# plugV6-Relay-NC_5x5cm_SMD0805-2.net
KiCad netlist of a schematic drawn in EAGLE
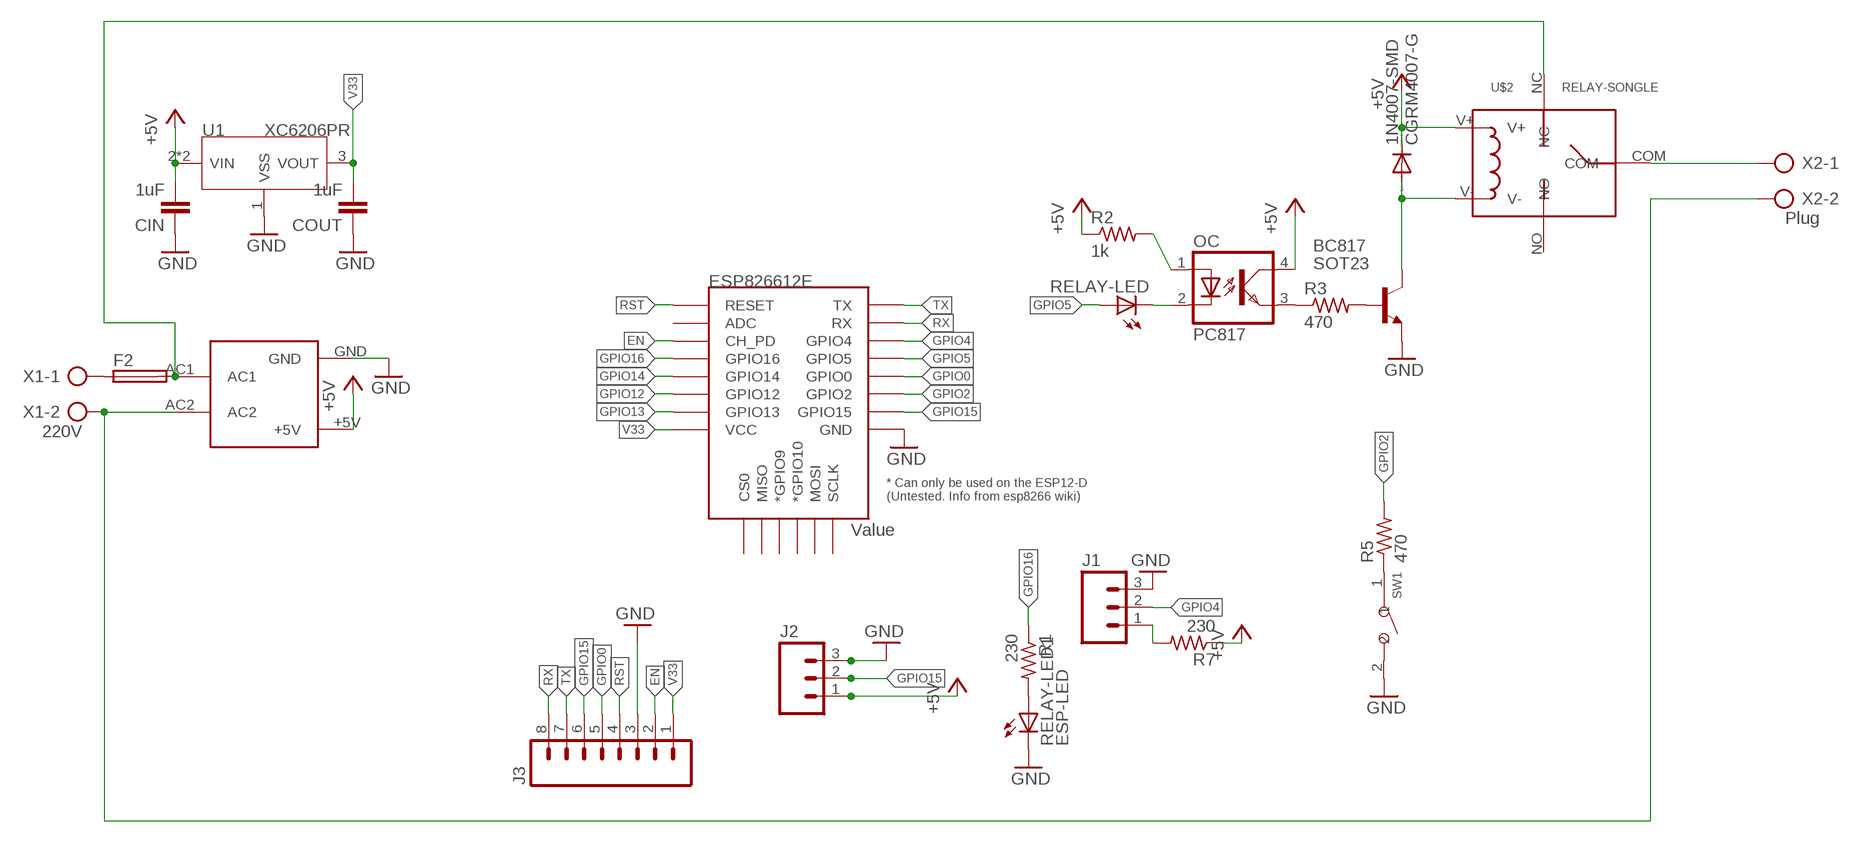
[diagram p0: schematic, sheet 1]

(export (version "E")
  (design (tool "Eeschema 10.0.6"))
  (components
    (comp (ref "1N4007-SMD")
      (value "CGRM4007-G")
      (footprint "eagle-import:SOD-123_MINI-SMA")
      (libsource (lib "eagle-import") (part "CGRM400-G7"))
    )
    (comp (ref "BC817")
      (value "SOT23")
      (footprint "eagle-import:SOT23-BEC")
      (libsource (lib "eagle-import") (part "-NPN-SOT23-BECBC817"))
    )
    (comp (ref "CIN")
      (value "1uF")
      (footprint "eagle-import:C0805")
      (libsource (lib "eagle-import") (part "C-EUC0805"))
    )
    (comp (ref "COUT")
      (value "1uF")
      (footprint "eagle-import:C0805")
      (libsource (lib "eagle-import") (part "C-EUC0805"))
    )
    (comp (ref "ESP826612E")
      (value "Value")
      (footprint "eagle-import:ESP12E-SMD")
      (libsource (lib "eagle-import") (part "ESP12ESMD"))
    )
    (comp (ref "F2")
      (value "TR5")
      (footprint "eagle-import:TR5")
      (libsource (lib "eagle-import") (part "TR5"))
    )
    (comp (ref "J1")
      (value "M03PTH")
      (footprint "eagle-import:1X03")
      (libsource (lib "eagle-import") (part "M03PTH"))
    )
    (comp (ref "J2")
      (value "M03PTH")
      (footprint "eagle-import:1X03")
      (libsource (lib "eagle-import") (part "M03PTH"))
    )
    (comp (ref "J3")
      (value "M08")
      (footprint "eagle-import:1X08_ROUND")
      (libsource (lib "eagle-import") (part "M08"))
    )
    (comp (ref "OC")
      (value "PC817")
      (footprint "eagle-import:DIL04")
      (fields (field (name "MPN") "PC817X4J000F"))
      (libsource (lib "eagle-import") (part "PC817"))
    )
    (comp (ref "R1")
      (value "230")
      (footprint "eagle-import:M0805")
      (libsource (lib "eagle-import") (part "R-US_M0805"))
    )
    (comp (ref "R2")
      (value "1k")
      (footprint "eagle-import:M0805")
      (libsource (lib "eagle-import") (part "R-US_M0805"))
    )
    (comp (ref "R3")
      (value "470")
      (footprint "eagle-import:M0805")
      (libsource (lib "eagle-import") (part "R-US_M0805"))
    )
    (comp (ref "R5")
      (value "470")
      (footprint "eagle-import:M0805")
      (libsource (lib "eagle-import") (part "R-US_M0805"))
    )
    (comp (ref "R7")
      (value "230")
      (footprint "eagle-import:M0805")
      (libsource (lib "eagle-import") (part "R-US_M0805"))
    )
    (comp (ref "RELAY-LED")
      (value "LEDCHIPLED_0805")
      (footprint "eagle-import:CHIPLED_0805")
      (libsource (lib "eagle-import") (part "LEDCHIPLED_0805"))
    )
    (comp (ref "RELAY-LED1")
      (value "ESP-LED")
      (footprint "eagle-import:CHIPLED_0805")
      (libsource (lib "eagle-import") (part "LEDCHIPLED_0805"))
    )
    (comp (ref "SW1")
      (value "DIP-BUTTON(2P-6.0X3.0X4.3MM)-TS-1101F")
      (footprint "eagle-import:SW2-5.0-6.0X3.0X4.3MM")
      (libsource (lib "eagle-import") (part "DIP-BUTTON(2P-6.0X3.0X4.3MM)-TS-1101F"))
    )
    (comp (ref "U$1")
      (value "HLK-PM01")
      (footprint "eagle-import:HLK-PM01")
      (libsource (lib "eagle-import") (part "HLK-PM01"))
    )
    (comp (ref "U$2")
      (value "RELAY-SONGLE")
      (footprint "eagle-import:RELAY-SONGLE")
      (libsource (lib "eagle-import") (part "RELAY-SONGLE"))
    )
    (comp (ref "U1")
      (value "XC6206PR")
      (footprint "eagle-import:SOT89")
      (libsource (lib "eagle-import") (part "XC6206PR"))
    )
    (comp (ref "X1")
      (value "220V")
      (footprint "eagle-import:AK300_2")
      (libsource (lib "eagle-import") (part "AK300/2"))
    )
    (comp (ref "X2")
      (value "Plug")
      (footprint "eagle-import:AK300_2")
      (libsource (lib "eagle-import") (part "AK300/2"))
    )
  )
  (nets
    (net (code "1") (name "+5V") (class "Default")
      (node (ref "1N4007-SMD") (pin "C") (pinfunction "C_C") (pintype "passive"))
      (node (ref "CIN") (pin "2") (pinfunction "2_2") (pintype "passive"))
      (node (ref "J2") (pin "1") (pinfunction "1_1") (pintype "passive"))
      (node (ref "OC") (pin "4") (pinfunction "COL_4") (pintype "passive"))
      (node (ref "R2") (pin "1") (pinfunction "1_1") (pintype "passive"))
      (node (ref "R7") (pin "1") (pinfunction "1_1") (pintype "passive"))
      (node (ref "U$1") (pin "+5V") (pinfunction "+5V_+5V") (pintype "bidirectional"))
      (node (ref "U$2") (pin "V+") (pinfunction "V+_V+") (pintype "bidirectional"))
      (node (ref "U1") (pin "2") (pinfunction "VIN_2") (pintype "input"))
      (node (ref "U1") (pin "4") (pinfunction "VIN_4") (pintype "input"))
    )
    (net (code "2") (name "EN") (class "Default")
      (node (ref "ESP826612E") (pin "CH_PD") (pinfunction "CH_PD_CH_PD") (pintype "bidirectional"))
      (node (ref "J3") (pin "2") (pinfunction "2_2") (pintype "passive"))
    )
    (net (code "3") (name "GND") (class "Default")
      (node (ref "BC817") (pin "E") (pinfunction "E_E") (pintype "passive"))
      (node (ref "CIN") (pin "1") (pinfunction "1_1") (pintype "passive"))
      (node (ref "COUT") (pin "1") (pinfunction "1_1") (pintype "passive"))
      (node (ref "ESP826612E") (pin "GND") (pinfunction "GND_GND") (pintype "bidirectional"))
      (node (ref "J1") (pin "3") (pinfunction "3_3") (pintype "passive"))
      (node (ref "J2") (pin "3") (pinfunction "3_3") (pintype "passive"))
      (node (ref "J3") (pin "3") (pinfunction "3_3") (pintype "passive"))
      (node (ref "RELAY-LED1") (pin "C") (pinfunction "C_C") (pintype "passive"))
      (node (ref "SW1") (pin "2") (pinfunction "2_2") (pintype "bidirectional"))
      (node (ref "U$1") (pin "GND") (pinfunction "GND_GND") (pintype "bidirectional"))
      (node (ref "U1") (pin "1") (pinfunction "VSS_1") (pintype "power_in"))
    )
    (net (code "4") (name "GPIO0") (class "Default")
      (node (ref "ESP826612E") (pin "GPIO0") (pinfunction "GPIO0_GPIO0") (pintype "bidirectional"))
      (node (ref "J3") (pin "5") (pinfunction "5_5") (pintype "passive"))
    )
    (net (code "5") (name "GPIO2") (class "Default")
      (node (ref "ESP826612E") (pin "GPIO2") (pinfunction "GPIO2_GPIO2") (pintype "bidirectional"))
      (node (ref "R5") (pin "2") (pinfunction "2_2") (pintype "passive"))
    )
    (net (code "6") (name "GPIO4") (class "Default")
      (node (ref "ESP826612E") (pin "GPIO4") (pinfunction "GPIO4_GPIO4") (pintype "bidirectional"))
      (node (ref "J1") (pin "2") (pinfunction "2_2") (pintype "passive"))
    )
    (net (code "7") (name "GPIO5") (class "Default")
      (node (ref "ESP826612E") (pin "GPIO5") (pinfunction "GPIO5_GPIO5") (pintype "bidirectional"))
      (node (ref "RELAY-LED") (pin "A") (pinfunction "A_A") (pintype "passive"))
    )
    (net (code "8") (name "GPIO12") (class "Default")
      (node (ref "ESP826612E") (pin "GPIO12") (pinfunction "GPIO12_GPIO12") (pintype "bidirectional"))
    )
    (net (code "9") (name "GPIO13") (class "Default")
      (node (ref "ESP826612E") (pin "GPIO13") (pinfunction "GPIO13_GPIO13") (pintype "bidirectional"))
    )
    (net (code "10") (name "GPIO14") (class "Default")
      (node (ref "ESP826612E") (pin "GPIO14") (pinfunction "GPIO14_GPIO14") (pintype "bidirectional"))
    )
    (net (code "11") (name "GPIO15") (class "Default")
      (node (ref "ESP826612E") (pin "GPIO15") (pinfunction "GPIO15_GPIO15") (pintype "bidirectional"))
      (node (ref "J2") (pin "2") (pinfunction "2_2") (pintype "passive"))
      (node (ref "J3") (pin "6") (pinfunction "6_6") (pintype "passive"))
    )
    (net (code "12") (name "GPIO16") (class "Default")
      (node (ref "ESP826612E") (pin "GPIO16") (pinfunction "GPIO16_GPIO16") (pintype "bidirectional"))
      (node (ref "R1") (pin "1") (pinfunction "1_1") (pintype "passive"))
    )
    (net (code "13") (name "Net-(1N4007-SMD-PadA)") (class "Default")
      (node (ref "1N4007-SMD") (pin "A") (pinfunction "A_A") (pintype "passive"))
      (node (ref "BC817") (pin "C") (pinfunction "C_C") (pintype "passive"))
      (node (ref "U$2") (pin "V-") (pinfunction "V-_V-") (pintype "bidirectional"))
    )
    (net (code "14") (name "Net-(BC817-PadB)") (class "Default")
      (node (ref "BC817") (pin "B") (pinfunction "B_B") (pintype "passive"))
      (node (ref "R3") (pin "2") (pinfunction "2_2") (pintype "passive"))
    )
    (net (code "15") (name "Net-(F2-Pad2)") (class "Default")
      (node (ref "F2") (pin "2") (pinfunction "2_2") (pintype "passive"))
      (node (ref "U$1") (pin "AC1") (pinfunction "AC1_AC1") (pintype "bidirectional"))
      (node (ref "U$2") (pin "NC") (pinfunction "NC_NC") (pintype "bidirectional"))
    )
    (net (code "16") (name "Net-(J1-Pad1)") (class "Default")
      (node (ref "J1") (pin "1") (pinfunction "1_1") (pintype "passive"))
      (node (ref "R7") (pin "2") (pinfunction "2_2") (pintype "passive"))
    )
    (net (code "17") (name "Net-(OC-A)") (class "Default")
      (node (ref "OC") (pin "1") (pinfunction "A_1") (pintype "passive"))
      (node (ref "R2") (pin "2") (pinfunction "2_2") (pintype "passive"))
    )
    (net (code "18") (name "Net-(OC-C)") (class "Default")
      (node (ref "OC") (pin "2") (pinfunction "C_2") (pintype "passive"))
      (node (ref "RELAY-LED") (pin "C") (pinfunction "C_C") (pintype "passive"))
    )
    (net (code "19") (name "Net-(OC-EMIT)") (class "Default")
      (node (ref "OC") (pin "3") (pinfunction "EMIT_3") (pintype "passive"))
      (node (ref "R3") (pin "1") (pinfunction "1_1") (pintype "passive"))
    )
    (net (code "20") (name "Net-(R1-Pad2)") (class "Default")
      (node (ref "R1") (pin "2") (pinfunction "2_2") (pintype "passive"))
      (node (ref "RELAY-LED1") (pin "A") (pinfunction "A_A") (pintype "passive"))
    )
    (net (code "21") (name "Net-(R5-Pad1)") (class "Default")
      (node (ref "R5") (pin "1") (pinfunction "1_1") (pintype "passive"))
      (node (ref "SW1") (pin "1") (pinfunction "1_1") (pintype "bidirectional"))
    )
    (net (code "22") (name "Net-(X1A-KL)") (class "Default")
      (node (ref "F2") (pin "1") (pinfunction "1_1") (pintype "passive"))
      (node (ref "X1") (pin "1") (pinfunction "KL_1") (pintype "passive"))
    )
    (net (code "23") (name "Net-(X1B-KL)") (class "Default")
      (node (ref "U$1") (pin "AC2") (pinfunction "AC2_AC2") (pintype "bidirectional"))
      (node (ref "X1") (pin "2") (pinfunction "KL_2") (pintype "passive"))
      (node (ref "X2") (pin "2") (pinfunction "KL_2") (pintype "passive"))
    )
    (net (code "24") (name "Net-(X2A-KL)") (class "Default")
      (node (ref "U$2") (pin "COM") (pinfunction "COM_COM") (pintype "bidirectional"))
      (node (ref "X2") (pin "1") (pinfunction "KL_1") (pintype "passive"))
    )
    (net (code "25") (name "RST") (class "Default")
      (node (ref "ESP826612E") (pin "RESET") (pinfunction "RESET_RESET") (pintype "bidirectional"))
      (node (ref "J3") (pin "4") (pinfunction "4_4") (pintype "passive"))
    )
    (net (code "26") (name "RX") (class "Default")
      (node (ref "ESP826612E") (pin "RXD0") (pinfunction "RX_RXD0") (pintype "bidirectional"))
      (node (ref "J3") (pin "8") (pinfunction "8_8") (pintype "passive"))
    )
    (net (code "27") (name "TX") (class "Default")
      (node (ref "ESP826612E") (pin "TXD0") (pinfunction "TX_TXD0") (pintype "bidirectional"))
      (node (ref "J3") (pin "7") (pinfunction "7_7") (pintype "passive"))
    )
    (net (code "28") (name "V33") (class "Default")
      (node (ref "COUT") (pin "2") (pinfunction "2_2") (pintype "passive"))
      (node (ref "ESP826612E") (pin "VCC") (pinfunction "VCC_VCC") (pintype "bidirectional"))
      (node (ref "J3") (pin "1") (pinfunction "1_1") (pintype "passive"))
      (node (ref "U1") (pin "3") (pinfunction "VOUT_3") (pintype "output"))
    )
    (net (code "29") (name "unconnected-(ESP826612E-*GPIO9-PadGPIO9)") (class "Default")
      (node (ref "ESP826612E") (pin "GPIO9") (pinfunction "*GPIO9_GPIO9") (pintype "bidirectional"))
    )
    (net (code "30") (name "unconnected-(ESP826612E-*GPIO10-PadGPIO10)") (class "Default")
      (node (ref "ESP826612E") (pin "GPIO10") (pinfunction "*GPIO10_GPIO10") (pintype "bidirectional"))
    )
    (net (code "31") (name "unconnected-(ESP826612E-PadADC)") (class "Default")
      (node (ref "ESP826612E") (pin "ADC") (pinfunction "ADC_ADC") (pintype "bidirectional"))
    )
    (net (code "32") (name "unconnected-(ESP826612E-PadCS0)") (class "Default")
      (node (ref "ESP826612E") (pin "CS0") (pinfunction "CS0_CS0") (pintype "bidirectional"))
    )
    (net (code "33") (name "unconnected-(ESP826612E-PadMISO)") (class "Default")
      (node (ref "ESP826612E") (pin "MISO") (pinfunction "MISO_MISO") (pintype "bidirectional"))
    )
    (net (code "34") (name "unconnected-(ESP826612E-PadMOSI)") (class "Default")
      (node (ref "ESP826612E") (pin "MOSI") (pinfunction "MOSI_MOSI") (pintype "bidirectional"))
    )
    (net (code "35") (name "unconnected-(ESP826612E-PadSCLK)") (class "Default")
      (node (ref "ESP826612E") (pin "SCLK") (pinfunction "SCLK_SCLK") (pintype "bidirectional"))
    )
    (net (code "36") (name "unconnected-(U$2-PadNO)") (class "Default")
      (node (ref "U$2") (pin "NO") (pinfunction "NO_NO") (pintype "bidirectional"))
    )
  )
)
